# slaveV11.net
KiCad netlist of a schematic drawn in EAGLE
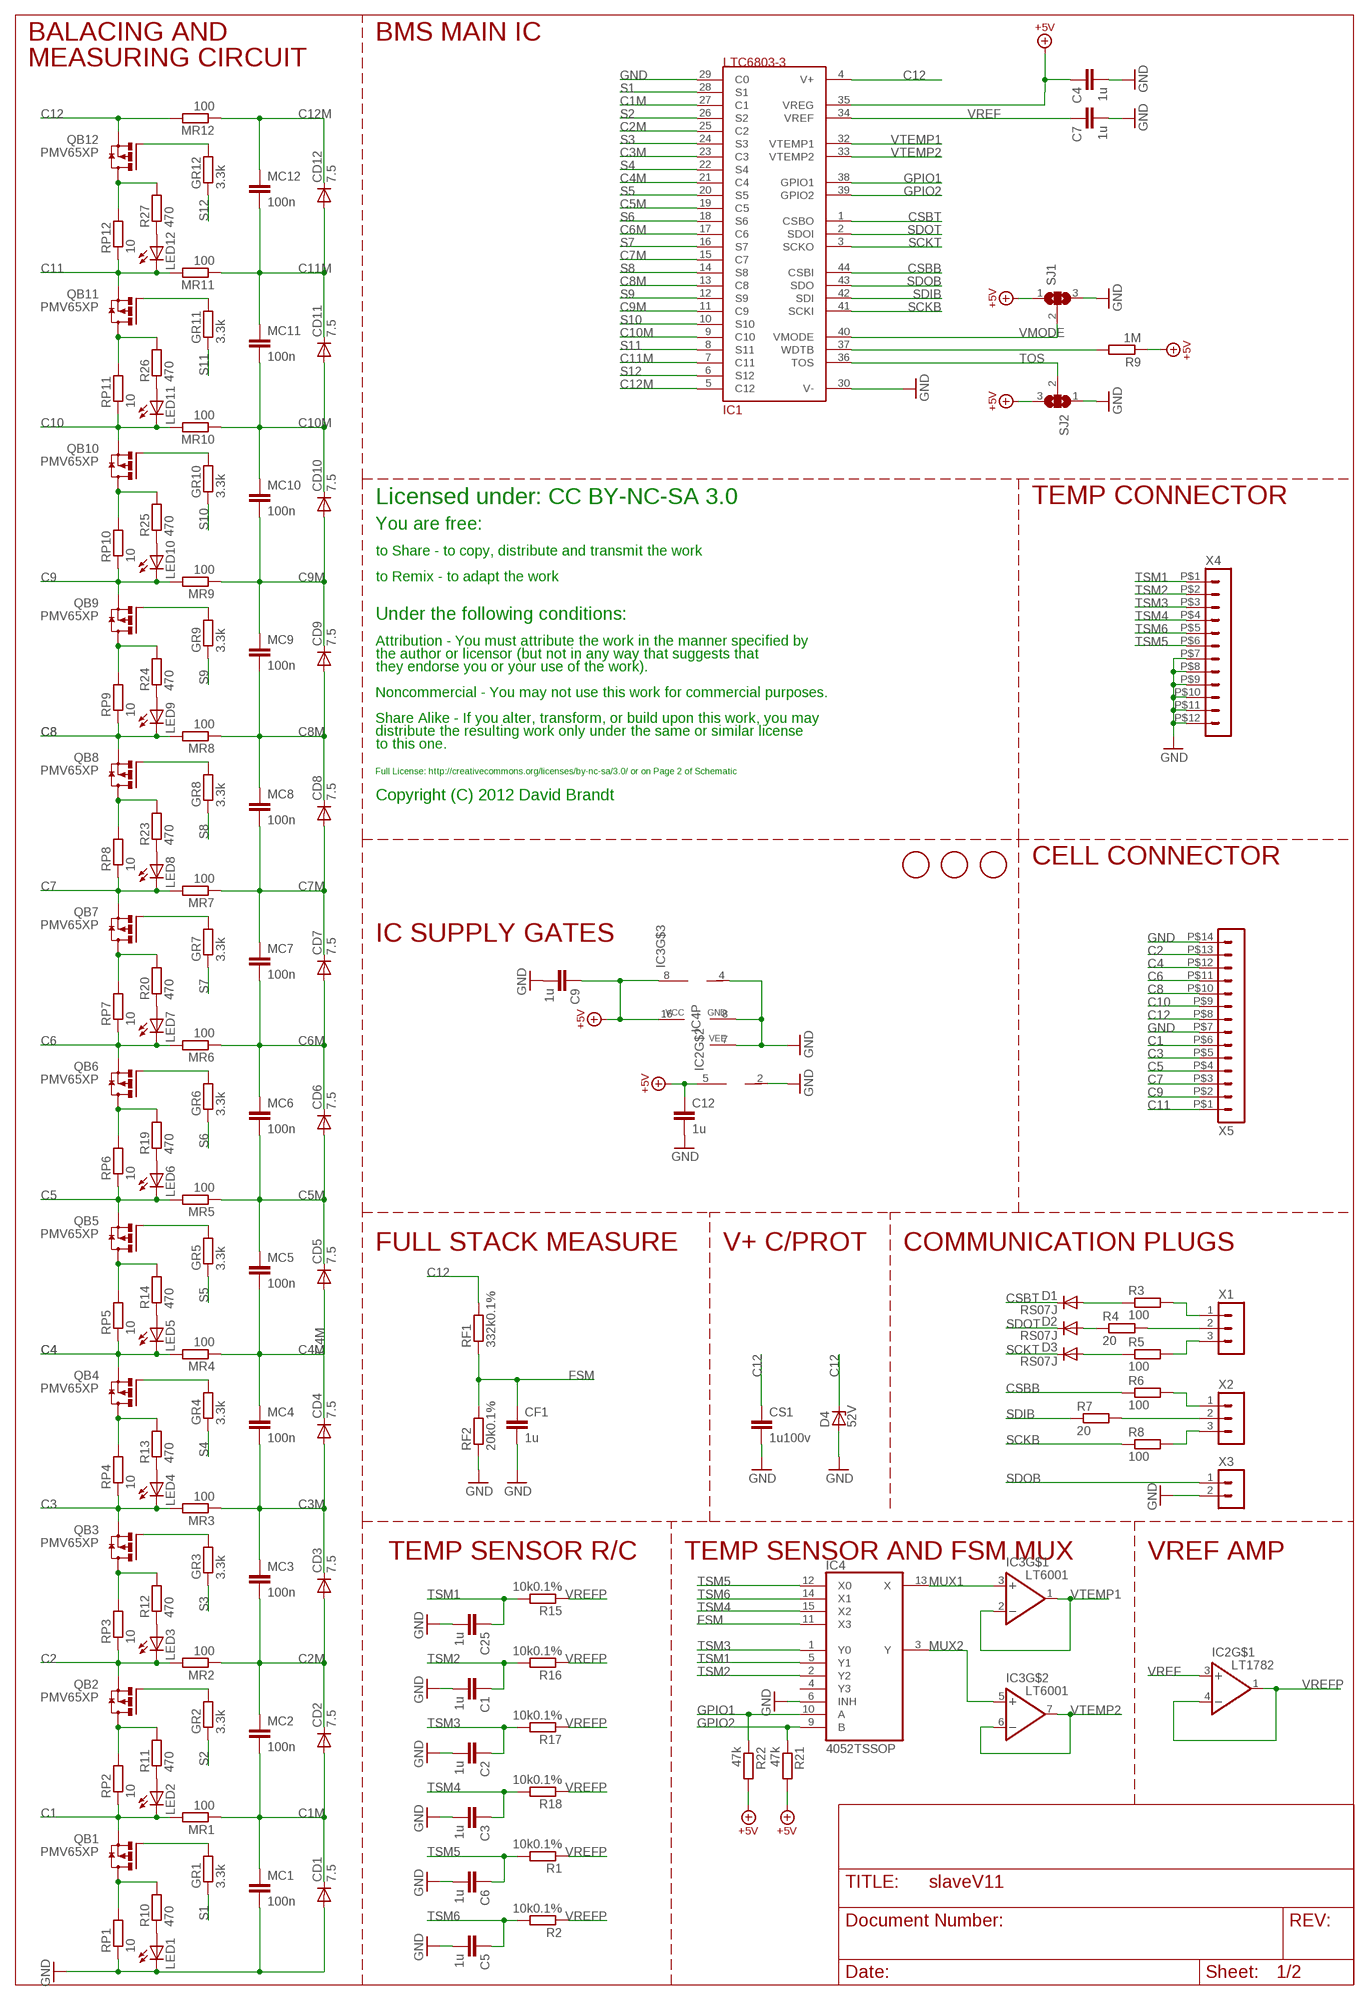
[diagram p0: schematic, sheet 1]
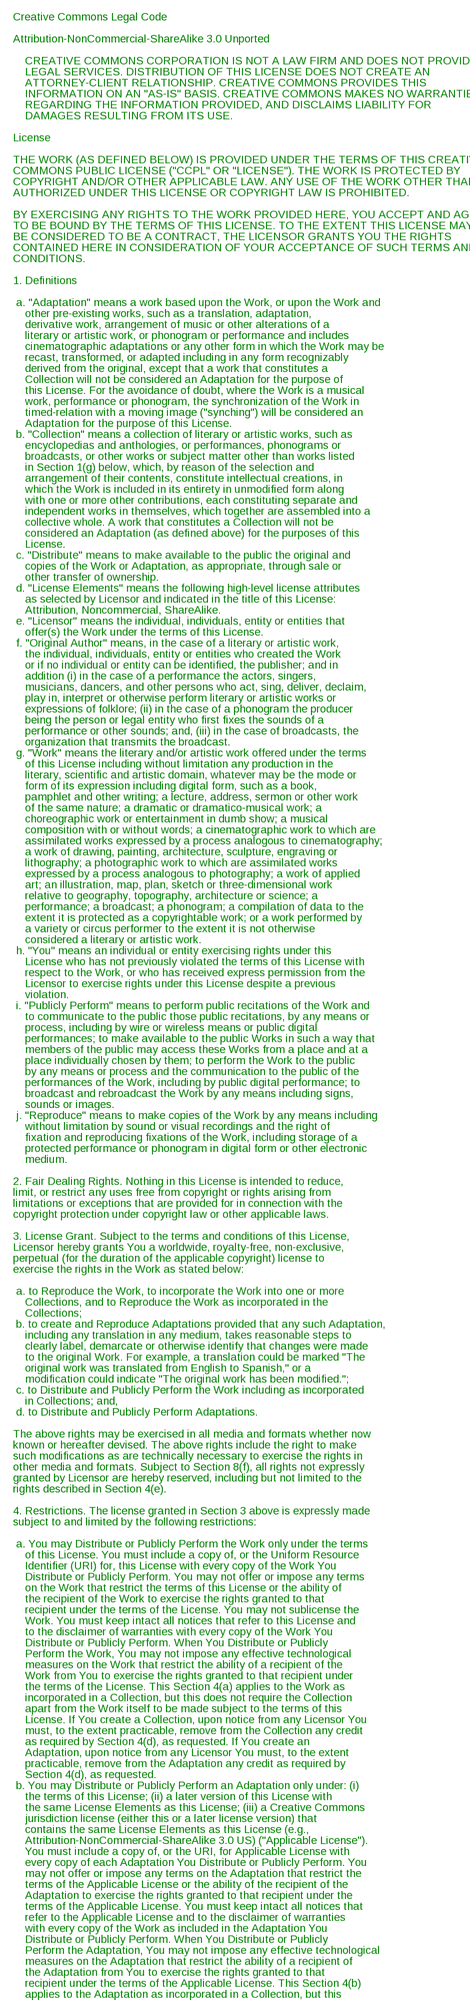
[diagram p1: schematic, sheet 2, part 1 of 2]
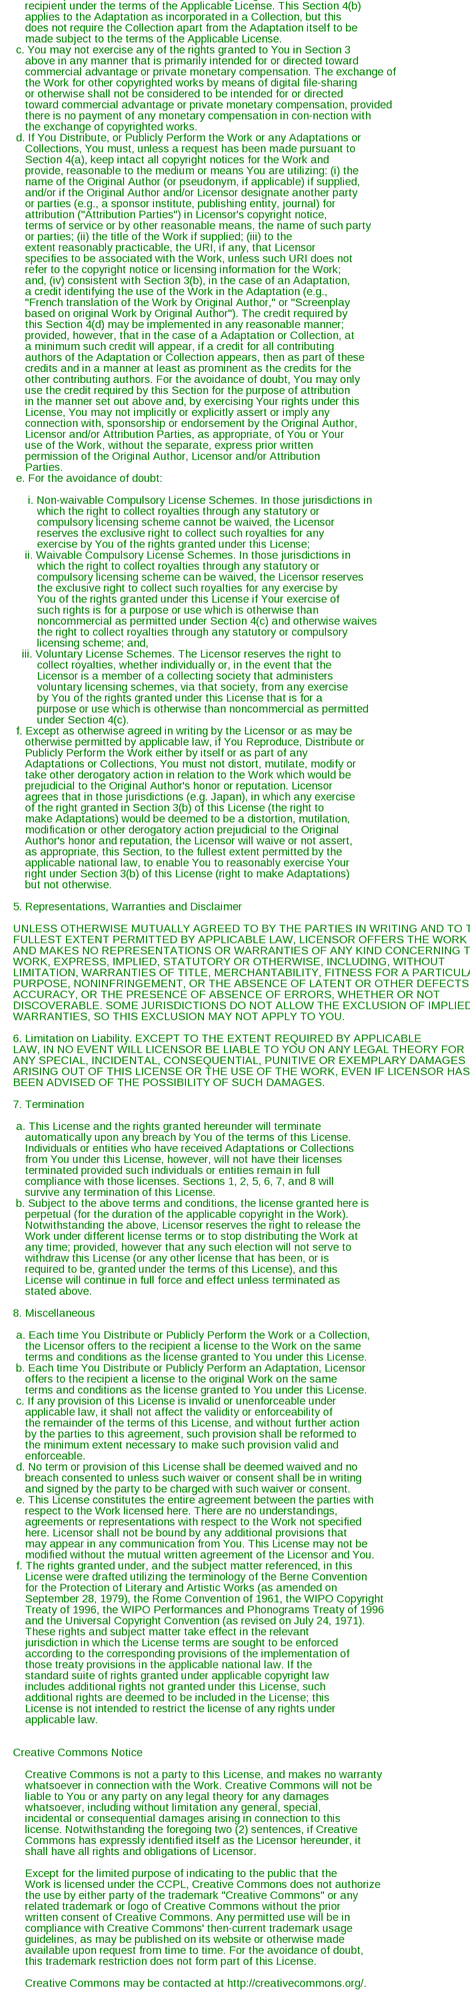
[diagram p2: schematic, sheet 2, part 2 of 2]

(export (version "E")
  (design (tool "Eeschema 10.0.6"))
  (components
    (comp (ref "C1")
      (value "1u")
      (footprint "eagle-import:C0603")
      (libsource (lib "eagle-import") (part "C-EUC0603"))
    )
    (comp (ref "C2")
      (value "1u")
      (footprint "eagle-import:C0603")
      (libsource (lib "eagle-import") (part "C-EUC0603"))
    )
    (comp (ref "C3")
      (value "1u")
      (footprint "eagle-import:C0603")
      (libsource (lib "eagle-import") (part "C-EUC0603"))
    )
    (comp (ref "C4")
      (value "1u")
      (footprint "eagle-import:C0603")
      (libsource (lib "eagle-import") (part "C-EUC0603"))
    )
    (comp (ref "C5")
      (value "1u")
      (footprint "eagle-import:C0603")
      (libsource (lib "eagle-import") (part "C-EUC0603"))
    )
    (comp (ref "C6")
      (value "1u")
      (footprint "eagle-import:C0603")
      (libsource (lib "eagle-import") (part "C-EUC0603"))
    )
    (comp (ref "C7")
      (value "1u")
      (footprint "eagle-import:C0603")
      (libsource (lib "eagle-import") (part "C-EUC0603"))
    )
    (comp (ref "C9")
      (value "1u")
      (footprint "eagle-import:C0603")
      (libsource (lib "eagle-import") (part "C-EUC0603"))
    )
    (comp (ref "C12")
      (value "1u")
      (footprint "eagle-import:C0603")
      (libsource (lib "eagle-import") (part "C-EUC0603"))
    )
    (comp (ref "C25")
      (value "1u")
      (footprint "eagle-import:C0603")
      (libsource (lib "eagle-import") (part "C-EUC0603"))
    )
    (comp (ref "CD1")
      (value "7.5")
      (footprint "eagle-import:SOD323-W")
      (libsource (lib "eagle-import") (part "DIODE-SOD323-W"))
    )
    (comp (ref "CD2")
      (value "7.5")
      (footprint "eagle-import:SOD323-W")
      (libsource (lib "eagle-import") (part "DIODE-SOD323-W"))
    )
    (comp (ref "CD3")
      (value "7.5")
      (footprint "eagle-import:SOD323-W")
      (libsource (lib "eagle-import") (part "DIODE-SOD323-W"))
    )
    (comp (ref "CD4")
      (value "7.5")
      (footprint "eagle-import:SOD323-W")
      (libsource (lib "eagle-import") (part "DIODE-SOD323-W"))
    )
    (comp (ref "CD5")
      (value "7.5")
      (footprint "eagle-import:SOD323-W")
      (libsource (lib "eagle-import") (part "DIODE-SOD323-W"))
    )
    (comp (ref "CD6")
      (value "7.5")
      (footprint "eagle-import:SOD323-W")
      (libsource (lib "eagle-import") (part "DIODE-SOD323-W"))
    )
    (comp (ref "CD7")
      (value "7.5")
      (footprint "eagle-import:SOD323-W")
      (libsource (lib "eagle-import") (part "DIODE-SOD323-W"))
    )
    (comp (ref "CD8")
      (value "7.5")
      (footprint "eagle-import:SOD323-W")
      (libsource (lib "eagle-import") (part "DIODE-SOD323-W"))
    )
    (comp (ref "CD9")
      (value "7.5")
      (footprint "eagle-import:SOD323-W")
      (libsource (lib "eagle-import") (part "DIODE-SOD323-W"))
    )
    (comp (ref "CD10")
      (value "7.5")
      (footprint "eagle-import:SOD323-W")
      (libsource (lib "eagle-import") (part "DIODE-SOD323-W"))
    )
    (comp (ref "CD11")
      (value "7.5")
      (footprint "eagle-import:SOD323-W")
      (libsource (lib "eagle-import") (part "DIODE-SOD323-W"))
    )
    (comp (ref "CD12")
      (value "7.5")
      (footprint "eagle-import:SOD323-W")
      (libsource (lib "eagle-import") (part "DIODE-SOD323-W"))
    )
    (comp (ref "CF1")
      (value "1u")
      (footprint "eagle-import:C0603")
      (libsource (lib "eagle-import") (part "C-EUC0603"))
    )
    (comp (ref "CS1")
      (value "1u100v")
      (footprint "eagle-import:C1206K")
      (libsource (lib "eagle-import") (part "C-EUC1206K"))
    )
    (comp (ref "D1")
      (value "RS07J")
      (footprint "eagle-import:DO-219AB")
      (libsource (lib "eagle-import") (part "RS07J"))
    )
    (comp (ref "D2")
      (value "RS07J")
      (footprint "eagle-import:DO-219AB")
      (libsource (lib "eagle-import") (part "RS07J"))
    )
    (comp (ref "D3")
      (value "RS07J")
      (footprint "eagle-import:DO-219AB")
      (libsource (lib "eagle-import") (part "RS07J"))
    )
    (comp (ref "D4")
      (value "52V")
      (footprint "eagle-import:SOD123")
      (libsource (lib "eagle-import") (part "ZENER-DIODESOD123"))
    )
    (comp (ref "GR1")
      (value "3.3k")
      (footprint "eagle-import:R0603")
      (libsource (lib "eagle-import") (part "rcl_R-EU_R0603"))
    )
    (comp (ref "GR2")
      (value "3.3k")
      (footprint "eagle-import:R0603")
      (libsource (lib "eagle-import") (part "rcl_R-EU_R0603"))
    )
    (comp (ref "GR3")
      (value "3.3k")
      (footprint "eagle-import:R0603")
      (libsource (lib "eagle-import") (part "rcl_R-EU_R0603"))
    )
    (comp (ref "GR4")
      (value "3.3k")
      (footprint "eagle-import:R0603")
      (libsource (lib "eagle-import") (part "rcl_R-EU_R0603"))
    )
    (comp (ref "GR5")
      (value "3.3k")
      (footprint "eagle-import:R0603")
      (libsource (lib "eagle-import") (part "rcl_R-EU_R0603"))
    )
    (comp (ref "GR6")
      (value "3.3k")
      (footprint "eagle-import:R0603")
      (libsource (lib "eagle-import") (part "rcl_R-EU_R0603"))
    )
    (comp (ref "GR7")
      (value "3.3k")
      (footprint "eagle-import:R0603")
      (libsource (lib "eagle-import") (part "rcl_R-EU_R0603"))
    )
    (comp (ref "GR8")
      (value "3.3k")
      (footprint "eagle-import:R0603")
      (libsource (lib "eagle-import") (part "rcl_R-EU_R0603"))
    )
    (comp (ref "GR9")
      (value "3.3k")
      (footprint "eagle-import:R0603")
      (libsource (lib "eagle-import") (part "rcl_R-EU_R0603"))
    )
    (comp (ref "GR10")
      (value "3.3k")
      (footprint "eagle-import:R0603")
      (libsource (lib "eagle-import") (part "rcl_R-EU_R0603"))
    )
    (comp (ref "GR11")
      (value "3.3k")
      (footprint "eagle-import:R0603")
      (libsource (lib "eagle-import") (part "rcl_R-EU_R0603"))
    )
    (comp (ref "GR12")
      (value "3.3k")
      (footprint "eagle-import:R0603")
      (libsource (lib "eagle-import") (part "rcl_R-EU_R0603"))
    )
    (comp (ref "IC1")
      (value "LTC6803-3")
      (footprint "eagle-import:44SSOP")
      (libsource (lib "eagle-import") (part "LTC6803-3"))
    )
    (comp (ref "IC2")
      (value "LT1782")
      (footprint "eagle-import:SOT23-5")
      (libsource (lib "eagle-import") (part "LT1782"))
    )
    (comp (ref "IC3")
      (value "LT6001")
      (footprint "eagle-import:MS8")
      (libsource (lib "eagle-import") (part "LT6004"))
    )
    (comp (ref "IC4")
      (value "4052TSSOP")
      (footprint "eagle-import:TSSOP16")
      (libsource (lib "eagle-import") (part "4052TSSOP"))
    )
    (comp (ref "LED1")
      (value "LEDCHIPLED_0805")
      (footprint "eagle-import:CHIPLED_0805")
      (libsource (lib "eagle-import") (part "LEDCHIPLED_0805"))
    )
    (comp (ref "LED2")
      (value "LEDCHIPLED_0805")
      (footprint "eagle-import:CHIPLED_0805")
      (libsource (lib "eagle-import") (part "LEDCHIPLED_0805"))
    )
    (comp (ref "LED3")
      (value "LEDCHIPLED_0805")
      (footprint "eagle-import:CHIPLED_0805")
      (libsource (lib "eagle-import") (part "LEDCHIPLED_0805"))
    )
    (comp (ref "LED4")
      (value "LEDCHIPLED_0805")
      (footprint "eagle-import:CHIPLED_0805")
      (libsource (lib "eagle-import") (part "LEDCHIPLED_0805"))
    )
    (comp (ref "LED5")
      (value "LEDCHIPLED_0805")
      (footprint "eagle-import:CHIPLED_0805")
      (libsource (lib "eagle-import") (part "LEDCHIPLED_0805"))
    )
    (comp (ref "LED6")
      (value "LEDCHIPLED_0805")
      (footprint "eagle-import:CHIPLED_0805")
      (libsource (lib "eagle-import") (part "LEDCHIPLED_0805"))
    )
    (comp (ref "LED7")
      (value "LEDCHIPLED_0805")
      (footprint "eagle-import:CHIPLED_0805")
      (libsource (lib "eagle-import") (part "LEDCHIPLED_0805"))
    )
    (comp (ref "LED8")
      (value "LEDCHIPLED_0805")
      (footprint "eagle-import:CHIPLED_0805")
      (libsource (lib "eagle-import") (part "LEDCHIPLED_0805"))
    )
    (comp (ref "LED9")
      (value "LEDCHIPLED_0805")
      (footprint "eagle-import:CHIPLED_0805")
      (libsource (lib "eagle-import") (part "LEDCHIPLED_0805"))
    )
    (comp (ref "LED10")
      (value "LEDCHIPLED_0805")
      (footprint "eagle-import:CHIPLED_0805")
      (libsource (lib "eagle-import") (part "LEDCHIPLED_0805"))
    )
    (comp (ref "LED11")
      (value "LEDCHIPLED_0805")
      (footprint "eagle-import:CHIPLED_0805")
      (libsource (lib "eagle-import") (part "LEDCHIPLED_0805"))
    )
    (comp (ref "LED12")
      (value "LEDCHIPLED_0805")
      (footprint "eagle-import:CHIPLED_0805")
      (libsource (lib "eagle-import") (part "LEDCHIPLED_0805"))
    )
    (comp (ref "MC1")
      (value "100n")
      (footprint "eagle-import:C1206")
      (libsource (lib "eagle-import") (part "C-EUC1206"))
    )
    (comp (ref "MC2")
      (value "100n")
      (footprint "eagle-import:C1206")
      (libsource (lib "eagle-import") (part "C-EUC1206"))
    )
    (comp (ref "MC3")
      (value "100n")
      (footprint "eagle-import:C1206")
      (libsource (lib "eagle-import") (part "C-EUC1206"))
    )
    (comp (ref "MC4")
      (value "100n")
      (footprint "eagle-import:C1206")
      (libsource (lib "eagle-import") (part "C-EUC1206"))
    )
    (comp (ref "MC5")
      (value "100n")
      (footprint "eagle-import:C1206")
      (libsource (lib "eagle-import") (part "C-EUC1206"))
    )
    (comp (ref "MC6")
      (value "100n")
      (footprint "eagle-import:C1206")
      (libsource (lib "eagle-import") (part "C-EUC1206"))
    )
    (comp (ref "MC7")
      (value "100n")
      (footprint "eagle-import:C1206")
      (libsource (lib "eagle-import") (part "C-EUC1206"))
    )
    (comp (ref "MC8")
      (value "100n")
      (footprint "eagle-import:C1206")
      (libsource (lib "eagle-import") (part "C-EUC1206"))
    )
    (comp (ref "MC9")
      (value "100n")
      (footprint "eagle-import:C1206")
      (libsource (lib "eagle-import") (part "C-EUC1206"))
    )
    (comp (ref "MC10")
      (value "100n")
      (footprint "eagle-import:C1206")
      (libsource (lib "eagle-import") (part "C-EUC1206"))
    )
    (comp (ref "MC11")
      (value "100n")
      (footprint "eagle-import:C1206")
      (libsource (lib "eagle-import") (part "C-EUC1206"))
    )
    (comp (ref "MC12")
      (value "100n")
      (footprint "eagle-import:C1206")
      (libsource (lib "eagle-import") (part "C-EUC1206"))
    )
    (comp (ref "MR1")
      (value "100")
      (footprint "eagle-import:R0603")
      (libsource (lib "eagle-import") (part "rcl_R-EU_R0603"))
    )
    (comp (ref "MR2")
      (value "100")
      (footprint "eagle-import:R0603")
      (libsource (lib "eagle-import") (part "rcl_R-EU_R0603"))
    )
    (comp (ref "MR3")
      (value "100")
      (footprint "eagle-import:R0603")
      (libsource (lib "eagle-import") (part "rcl_R-EU_R0603"))
    )
    (comp (ref "MR4")
      (value "100")
      (footprint "eagle-import:R0603")
      (libsource (lib "eagle-import") (part "rcl_R-EU_R0603"))
    )
    (comp (ref "MR5")
      (value "100")
      (footprint "eagle-import:R0603")
      (libsource (lib "eagle-import") (part "rcl_R-EU_R0603"))
    )
    (comp (ref "MR6")
      (value "100")
      (footprint "eagle-import:R0603")
      (libsource (lib "eagle-import") (part "rcl_R-EU_R0603"))
    )
    (comp (ref "MR7")
      (value "100")
      (footprint "eagle-import:R0603")
      (libsource (lib "eagle-import") (part "rcl_R-EU_R0603"))
    )
    (comp (ref "MR8")
      (value "100")
      (footprint "eagle-import:R0603")
      (libsource (lib "eagle-import") (part "rcl_R-EU_R0603"))
    )
    (comp (ref "MR9")
      (value "100")
      (footprint "eagle-import:R0603")
      (libsource (lib "eagle-import") (part "rcl_R-EU_R0603"))
    )
    (comp (ref "MR10")
      (value "100")
      (footprint "eagle-import:R0603")
      (libsource (lib "eagle-import") (part "rcl_R-EU_R0603"))
    )
    (comp (ref "MR11")
      (value "100")
      (footprint "eagle-import:R0603")
      (libsource (lib "eagle-import") (part "rcl_R-EU_R0603"))
    )
    (comp (ref "MR12")
      (value "100")
      (footprint "eagle-import:R0603")
      (libsource (lib "eagle-import") (part "rcl_R-EU_R0603"))
    )
    (comp (ref "QB1")
      (value "PMV65XP")
      (footprint "eagle-import:SUPER-SOT3")
      (libsource (lib "eagle-import") (part "FDN360P"))
    )
    (comp (ref "QB2")
      (value "PMV65XP")
      (footprint "eagle-import:SUPER-SOT3")
      (libsource (lib "eagle-import") (part "FDN360P"))
    )
    (comp (ref "QB3")
      (value "PMV65XP")
      (footprint "eagle-import:SUPER-SOT3")
      (libsource (lib "eagle-import") (part "FDN360P"))
    )
    (comp (ref "QB4")
      (value "PMV65XP")
      (footprint "eagle-import:SUPER-SOT3")
      (libsource (lib "eagle-import") (part "FDN360P"))
    )
    (comp (ref "QB5")
      (value "PMV65XP")
      (footprint "eagle-import:SUPER-SOT3")
      (libsource (lib "eagle-import") (part "FDN360P"))
    )
    (comp (ref "QB6")
      (value "PMV65XP")
      (footprint "eagle-import:SUPER-SOT3")
      (libsource (lib "eagle-import") (part "FDN360P"))
    )
    (comp (ref "QB7")
      (value "PMV65XP")
      (footprint "eagle-import:SUPER-SOT3")
      (libsource (lib "eagle-import") (part "FDN360P"))
    )
    (comp (ref "QB8")
      (value "PMV65XP")
      (footprint "eagle-import:SUPER-SOT3")
      (libsource (lib "eagle-import") (part "FDN360P"))
    )
    (comp (ref "QB9")
      (value "PMV65XP")
      (footprint "eagle-import:SUPER-SOT3")
      (libsource (lib "eagle-import") (part "FDN360P"))
    )
    (comp (ref "QB10")
      (value "PMV65XP")
      (footprint "eagle-import:SUPER-SOT3")
      (libsource (lib "eagle-import") (part "FDN360P"))
    )
    (comp (ref "QB11")
      (value "PMV65XP")
      (footprint "eagle-import:SUPER-SOT3")
      (libsource (lib "eagle-import") (part "FDN360P"))
    )
    (comp (ref "QB12")
      (value "PMV65XP")
      (footprint "eagle-import:SUPER-SOT3")
      (libsource (lib "eagle-import") (part "FDN360P"))
    )
    (comp (ref "R1")
      (value "10k0.1%")
      (footprint "eagle-import:R0603")
      (libsource (lib "eagle-import") (part "rcl_R-EU_R0603"))
    )
    (comp (ref "R2")
      (value "10k0.1%")
      (footprint "eagle-import:R0603")
      (libsource (lib "eagle-import") (part "rcl_R-EU_R0603"))
    )
    (comp (ref "R3")
      (value "100")
      (footprint "eagle-import:R0805")
      (libsource (lib "eagle-import") (part "rcl_R-EU_R0805"))
    )
    (comp (ref "R4")
      (value "20")
      (footprint "eagle-import:R0805")
      (libsource (lib "eagle-import") (part "rcl_R-EU_R0805"))
    )
    (comp (ref "R5")
      (value "100")
      (footprint "eagle-import:R0805")
      (libsource (lib "eagle-import") (part "rcl_R-EU_R0805"))
    )
    (comp (ref "R6")
      (value "100")
      (footprint "eagle-import:R0805")
      (libsource (lib "eagle-import") (part "rcl_R-EU_R0805"))
    )
    (comp (ref "R7")
      (value "20")
      (footprint "eagle-import:R0805")
      (libsource (lib "eagle-import") (part "rcl_R-EU_R0805"))
    )
    (comp (ref "R8")
      (value "100")
      (footprint "eagle-import:R0805")
      (libsource (lib "eagle-import") (part "rcl_R-EU_R0805"))
    )
    (comp (ref "R9")
      (value "1M")
      (footprint "eagle-import:R0603")
      (libsource (lib "eagle-import") (part "rcl_R-EU_R0603"))
    )
    (comp (ref "R10")
      (value "470")
      (footprint "eagle-import:R0603")
      (libsource (lib "eagle-import") (part "rcl_R-EU_R0603"))
    )
    (comp (ref "R11")
      (value "470")
      (footprint "eagle-import:R0603")
      (libsource (lib "eagle-import") (part "rcl_R-EU_R0603"))
    )
    (comp (ref "R12")
      (value "470")
      (footprint "eagle-import:R0603")
      (libsource (lib "eagle-import") (part "rcl_R-EU_R0603"))
    )
    (comp (ref "R13")
      (value "470")
      (footprint "eagle-import:R0603")
      (libsource (lib "eagle-import") (part "rcl_R-EU_R0603"))
    )
    (comp (ref "R14")
      (value "470")
      (footprint "eagle-import:R0603")
      (libsource (lib "eagle-import") (part "rcl_R-EU_R0603"))
    )
    (comp (ref "R15")
      (value "10k0.1%")
      (footprint "eagle-import:R0603")
      (libsource (lib "eagle-import") (part "rcl_R-EU_R0603"))
    )
    (comp (ref "R16")
      (value "10k0.1%")
      (footprint "eagle-import:R0603")
      (libsource (lib "eagle-import") (part "rcl_R-EU_R0603"))
    )
    (comp (ref "R17")
      (value "10k0.1%")
      (footprint "eagle-import:R0603")
      (libsource (lib "eagle-import") (part "rcl_R-EU_R0603"))
    )
    (comp (ref "R18")
      (value "10k0.1%")
      (footprint "eagle-import:R0603")
      (libsource (lib "eagle-import") (part "rcl_R-EU_R0603"))
    )
    (comp (ref "R19")
      (value "470")
      (footprint "eagle-import:R0603")
      (libsource (lib "eagle-import") (part "rcl_R-EU_R0603"))
    )
    (comp (ref "R20")
      (value "470")
      (footprint "eagle-import:R0603")
      (libsource (lib "eagle-import") (part "rcl_R-EU_R0603"))
    )
    (comp (ref "R21")
      (value "47k")
      (footprint "eagle-import:R0603")
      (libsource (lib "eagle-import") (part "rcl_R-EU_R0603"))
    )
    (comp (ref "R22")
      (value "47k")
      (footprint "eagle-import:R0603")
      (libsource (lib "eagle-import") (part "rcl_R-EU_R0603"))
    )
    (comp (ref "R23")
      (value "470")
      (footprint "eagle-import:R0603")
      (libsource (lib "eagle-import") (part "rcl_R-EU_R0603"))
    )
    (comp (ref "R24")
      (value "470")
      (footprint "eagle-import:R0603")
      (libsource (lib "eagle-import") (part "rcl_R-EU_R0603"))
    )
    (comp (ref "R25")
      (value "470")
      (footprint "eagle-import:R0603")
      (libsource (lib "eagle-import") (part "rcl_R-EU_R0603"))
    )
    (comp (ref "R26")
      (value "470")
      (footprint "eagle-import:R0603")
      (libsource (lib "eagle-import") (part "rcl_R-EU_R0603"))
    )
    (comp (ref "R27")
      (value "470")
      (footprint "eagle-import:R0603")
      (libsource (lib "eagle-import") (part "rcl_R-EU_R0603"))
    )
    (comp (ref "REF1")
      (value "FIDUCIALMOUNT")
      (footprint "eagle-import:FIDUCIA-MOUNT")
      (libsource (lib "eagle-import") (part "FIDUCIALMOUNT"))
    )
    (comp (ref "REF2")
      (value "FIDUCIALMOUNT")
      (footprint "eagle-import:FIDUCIA-MOUNT")
      (libsource (lib "eagle-import") (part "FIDUCIALMOUNT"))
    )
    (comp (ref "REF3")
      (value "FIDUCIALMOUNT")
      (footprint "eagle-import:FIDUCIA-MOUNT")
      (libsource (lib "eagle-import") (part "FIDUCIALMOUNT"))
    )
    (comp (ref "RF1")
      (value "332k0.1%")
      (footprint "eagle-import:R0603")
      (libsource (lib "eagle-import") (part "rcl_R-EU_R0603"))
    )
    (comp (ref "RF2")
      (value "20k0.1%")
      (footprint "eagle-import:R0603")
      (libsource (lib "eagle-import") (part "rcl_R-EU_R0603"))
    )
    (comp (ref "RP1")
      (value "10")
      (footprint "eagle-import:SM_3")
      (libsource (lib "eagle-import") (part "R-EU_SM_3"))
    )
    (comp (ref "RP2")
      (value "10")
      (footprint "eagle-import:SM_3")
      (libsource (lib "eagle-import") (part "R-EU_SM_3"))
    )
    (comp (ref "RP3")
      (value "10")
      (footprint "eagle-import:SM_3")
      (libsource (lib "eagle-import") (part "R-EU_SM_3"))
    )
    (comp (ref "RP4")
      (value "10")
      (footprint "eagle-import:SM_3")
      (libsource (lib "eagle-import") (part "R-EU_SM_3"))
    )
    (comp (ref "RP5")
      (value "10")
      (footprint "eagle-import:SM_3")
      (libsource (lib "eagle-import") (part "R-EU_SM_3"))
    )
    (comp (ref "RP6")
      (value "10")
      (footprint "eagle-import:SM_3")
      (libsource (lib "eagle-import") (part "R-EU_SM_3"))
    )
    (comp (ref "RP7")
      (value "10")
      (footprint "eagle-import:SM_3")
      (libsource (lib "eagle-import") (part "R-EU_SM_3"))
    )
    (comp (ref "RP8")
      (value "10")
      (footprint "eagle-import:SM_3")
      (libsource (lib "eagle-import") (part "R-EU_SM_3"))
    )
    (comp (ref "RP9")
      (value "10")
      (footprint "eagle-import:SM_3")
      (libsource (lib "eagle-import") (part "R-EU_SM_3"))
    )
    (comp (ref "RP10")
      (value "10")
      (footprint "eagle-import:SM_3")
      (libsource (lib "eagle-import") (part "R-EU_SM_3"))
    )
    (comp (ref "RP11")
      (value "10")
      (footprint "eagle-import:SM_3")
      (libsource (lib "eagle-import") (part "R-EU_SM_3"))
    )
    (comp (ref "RP12")
      (value "10")
      (footprint "eagle-import:SM_3")
      (libsource (lib "eagle-import") (part "R-EU_SM_3"))
    )
    (comp (ref "SJ1")
      (value "SJ2W")
      (footprint "eagle-import:SJ_2")
      (libsource (lib "eagle-import") (part "SJ2W"))
    )
    (comp (ref "SJ2")
      (value "SJ2W")
      (footprint "eagle-import:SJ_2")
      (libsource (lib "eagle-import") (part "SJ2W"))
    )
    (comp (ref "X1")
      (value "HEADER_POS3_43650-0315")
      (footprint "eagle-import:43650-0315")
      (libsource (lib "eagle-import") (part "HEADER_POS3_?43650-0315"))
    )
    (comp (ref "X2")
      (value "HEADER_POS3_43650-0315")
      (footprint "eagle-import:43650-0315")
      (libsource (lib "eagle-import") (part "HEADER_POS3_?43650-0315"))
    )
    (comp (ref "X3")
      (value "HEADER_POS2_43650-0215")
      (footprint "eagle-import:43650-0215")
      (libsource (lib "eagle-import") (part "HEADER_POS2_?43650-0215"))
    )
    (comp (ref "X4")
      (value "HEADER_POS12_43045-1212")
      (footprint "eagle-import:43045-1212")
      (libsource (lib "eagle-import") (part "HEADER_POS12_?43045-1212"))
    )
    (comp (ref "X5")
      (value "HEADER_POS14_43045-1412")
      (footprint "eagle-import:43045-1412")
      (libsource (lib "eagle-import") (part "HEADER_POS14_?43045-1412"))
    )
  )
  (nets
    (net (code "1") (name "+5V") (class "Default")
      (node (ref "C12") (pin "1") (pinfunction "1_1") (pintype "passive"))
      (node (ref "C4") (pin "1") (pinfunction "1_1") (pintype "passive"))
      (node (ref "C9") (pin "1") (pinfunction "1_1") (pintype "passive"))
      (node (ref "IC1") (pin "35") (pinfunction "VREG_35") (pintype "bidirectional"))
      (node (ref "IC2") (pin "5") (pinfunction "V+_5") (pintype "power_in"))
      (node (ref "IC3") (pin "8") (pinfunction "V+_8") (pintype "power_in"))
      (node (ref "IC4") (pin "16") (pinfunction "VCC_16") (pintype "power_in"))
      (node (ref "R21") (pin "2") (pinfunction "2_2") (pintype "passive"))
      (node (ref "R22") (pin "2") (pinfunction "2_2") (pintype "passive"))
      (node (ref "R9") (pin "1") (pinfunction "1_1") (pintype "passive"))
      (node (ref "SJ1") (pin "1") (pinfunction "1_1") (pintype "passive"))
      (node (ref "SJ2") (pin "3") (pinfunction "3_3") (pintype "passive"))
    )
    (net (code "2") (name "C1") (class "Default")
      (node (ref "LED2") (pin "C") (pinfunction "C_C") (pintype "passive"))
      (node (ref "MR1") (pin "2") (pinfunction "2_2") (pintype "passive"))
      (node (ref "QB1") (pin "2") (pinfunction "S_2") (pintype "passive"))
      (node (ref "RP2") (pin "P$1") (pinfunction "1_P$1") (pintype "passive"))
      (node (ref "X5") (pin "P$6") (pinfunction "6_P$6") (pintype "passive"))
    )
    (net (code "3") (name "C1M") (class "Default")
      (node (ref "CD1") (pin "C") (pinfunction "C_C") (pintype "passive"))
      (node (ref "CD2") (pin "A") (pinfunction "A_A") (pintype "passive"))
      (node (ref "IC1") (pin "27") (pinfunction "C1_27") (pintype "bidirectional"))
      (node (ref "MC1") (pin "1") (pinfunction "1_1") (pintype "passive"))
      (node (ref "MC2") (pin "2") (pinfunction "2_2") (pintype "passive"))
      (node (ref "MR1") (pin "1") (pinfunction "1_1") (pintype "passive"))
    )
    (net (code "4") (name "C2") (class "Default")
      (node (ref "LED3") (pin "C") (pinfunction "C_C") (pintype "passive"))
      (node (ref "MR2") (pin "2") (pinfunction "2_2") (pintype "passive"))
      (node (ref "QB2") (pin "2") (pinfunction "S_2") (pintype "passive"))
      (node (ref "RP3") (pin "P$1") (pinfunction "1_P$1") (pintype "passive"))
      (node (ref "X5") (pin "P$13") (pinfunction "13_P$13") (pintype "passive"))
    )
    (net (code "5") (name "C2M") (class "Default")
      (node (ref "CD2") (pin "C") (pinfunction "C_C") (pintype "passive"))
      (node (ref "CD3") (pin "A") (pinfunction "A_A") (pintype "passive"))
      (node (ref "IC1") (pin "25") (pinfunction "C2_25") (pintype "bidirectional"))
      (node (ref "MC2") (pin "1") (pinfunction "1_1") (pintype "passive"))
      (node (ref "MC3") (pin "2") (pinfunction "2_2") (pintype "passive"))
      (node (ref "MR2") (pin "1") (pinfunction "1_1") (pintype "passive"))
    )
    (net (code "6") (name "C3") (class "Default")
      (node (ref "LED4") (pin "C") (pinfunction "C_C") (pintype "passive"))
      (node (ref "MR3") (pin "2") (pinfunction "2_2") (pintype "passive"))
      (node (ref "QB3") (pin "2") (pinfunction "S_2") (pintype "passive"))
      (node (ref "RP4") (pin "P$1") (pinfunction "1_P$1") (pintype "passive"))
      (node (ref "X5") (pin "P$5") (pinfunction "5_P$5") (pintype "passive"))
    )
    (net (code "7") (name "C3M") (class "Default")
      (node (ref "CD3") (pin "C") (pinfunction "C_C") (pintype "passive"))
      (node (ref "CD4") (pin "A") (pinfunction "A_A") (pintype "passive"))
      (node (ref "IC1") (pin "23") (pinfunction "C3_23") (pintype "bidirectional"))
      (node (ref "MC3") (pin "1") (pinfunction "1_1") (pintype "passive"))
      (node (ref "MC4") (pin "2") (pinfunction "2_2") (pintype "passive"))
      (node (ref "MR3") (pin "1") (pinfunction "1_1") (pintype "passive"))
    )
    (net (code "8") (name "C4") (class "Default")
      (node (ref "LED5") (pin "C") (pinfunction "C_C") (pintype "passive"))
      (node (ref "MR4") (pin "2") (pinfunction "2_2") (pintype "passive"))
      (node (ref "QB4") (pin "2") (pinfunction "S_2") (pintype "passive"))
      (node (ref "RP5") (pin "P$1") (pinfunction "1_P$1") (pintype "passive"))
      (node (ref "X5") (pin "P$12") (pinfunction "12_P$12") (pintype "passive"))
    )
    (net (code "9") (name "C4M") (class "Default")
      (node (ref "CD4") (pin "C") (pinfunction "C_C") (pintype "passive"))
      (node (ref "CD5") (pin "A") (pinfunction "A_A") (pintype "passive"))
      (node (ref "IC1") (pin "21") (pinfunction "C4_21") (pintype "bidirectional"))
      (node (ref "MC4") (pin "1") (pinfunction "1_1") (pintype "passive"))
      (node (ref "MC5") (pin "2") (pinfunction "2_2") (pintype "passive"))
      (node (ref "MR4") (pin "1") (pinfunction "1_1") (pintype "passive"))
    )
    (net (code "10") (name "C5") (class "Default")
      (node (ref "LED6") (pin "C") (pinfunction "C_C") (pintype "passive"))
      (node (ref "MR5") (pin "2") (pinfunction "2_2") (pintype "passive"))
      (node (ref "QB5") (pin "2") (pinfunction "S_2") (pintype "passive"))
      (node (ref "RP6") (pin "P$1") (pinfunction "1_P$1") (pintype "passive"))
      (node (ref "X5") (pin "P$4") (pinfunction "4_P$4") (pintype "passive"))
    )
    (net (code "11") (name "C5M") (class "Default")
      (node (ref "CD5") (pin "C") (pinfunction "C_C") (pintype "passive"))
      (node (ref "CD6") (pin "A") (pinfunction "A_A") (pintype "passive"))
      (node (ref "IC1") (pin "19") (pinfunction "C5_19") (pintype "bidirectional"))
      (node (ref "MC5") (pin "1") (pinfunction "1_1") (pintype "passive"))
      (node (ref "MC6") (pin "2") (pinfunction "2_2") (pintype "passive"))
      (node (ref "MR5") (pin "1") (pinfunction "1_1") (pintype "passive"))
    )
    (net (code "12") (name "C6") (class "Default")
      (node (ref "LED7") (pin "C") (pinfunction "C_C") (pintype "passive"))
      (node (ref "MR6") (pin "2") (pinfunction "2_2") (pintype "passive"))
      (node (ref "QB6") (pin "2") (pinfunction "S_2") (pintype "passive"))
      (node (ref "RP7") (pin "P$1") (pinfunction "1_P$1") (pintype "passive"))
      (node (ref "X5") (pin "P$11") (pinfunction "11_P$11") (pintype "passive"))
    )
    (net (code "13") (name "C6M") (class "Default")
      (node (ref "CD6") (pin "C") (pinfunction "C_C") (pintype "passive"))
      (node (ref "CD7") (pin "A") (pinfunction "A_A") (pintype "passive"))
      (node (ref "IC1") (pin "17") (pinfunction "C6_17") (pintype "bidirectional"))
      (node (ref "MC6") (pin "1") (pinfunction "1_1") (pintype "passive"))
      (node (ref "MC7") (pin "2") (pinfunction "2_2") (pintype "passive"))
      (node (ref "MR6") (pin "1") (pinfunction "1_1") (pintype "passive"))
    )
    (net (code "14") (name "C7") (class "Default")
      (node (ref "LED8") (pin "C") (pinfunction "C_C") (pintype "passive"))
      (node (ref "MR7") (pin "2") (pinfunction "2_2") (pintype "passive"))
      (node (ref "QB7") (pin "2") (pinfunction "S_2") (pintype "passive"))
      (node (ref "RP8") (pin "P$1") (pinfunction "1_P$1") (pintype "passive"))
      (node (ref "X5") (pin "P$3") (pinfunction "3_P$3") (pintype "passive"))
    )
    (net (code "15") (name "C7M") (class "Default")
      (node (ref "CD7") (pin "C") (pinfunction "C_C") (pintype "passive"))
      (node (ref "CD8") (pin "A") (pinfunction "A_A") (pintype "passive"))
      (node (ref "IC1") (pin "15") (pinfunction "C7_15") (pintype "bidirectional"))
      (node (ref "MC7") (pin "1") (pinfunction "1_1") (pintype "passive"))
      (node (ref "MC8") (pin "2") (pinfunction "2_2") (pintype "passive"))
      (node (ref "MR7") (pin "1") (pinfunction "1_1") (pintype "passive"))
    )
    (net (code "16") (name "C8") (class "Default")
      (node (ref "LED9") (pin "C") (pinfunction "C_C") (pintype "passive"))
      (node (ref "MR8") (pin "2") (pinfunction "2_2") (pintype "passive"))
      (node (ref "QB8") (pin "2") (pinfunction "S_2") (pintype "passive"))
      (node (ref "RP9") (pin "P$1") (pinfunction "1_P$1") (pintype "passive"))
      (node (ref "X5") (pin "P$10") (pinfunction "10_P$10") (pintype "passive"))
    )
    (net (code "17") (name "C8M") (class "Default")
      (node (ref "CD8") (pin "C") (pinfunction "C_C") (pintype "passive"))
      (node (ref "CD9") (pin "A") (pinfunction "A_A") (pintype "passive"))
      (node (ref "IC1") (pin "13") (pinfunction "C8_13") (pintype "bidirectional"))
      (node (ref "MC8") (pin "1") (pinfunction "1_1") (pintype "passive"))
      (node (ref "MC9") (pin "2") (pinfunction "2_2") (pintype "passive"))
      (node (ref "MR8") (pin "1") (pinfunction "1_1") (pintype "passive"))
    )
    (net (code "18") (name "C9") (class "Default")
      (node (ref "LED10") (pin "C") (pinfunction "C_C") (pintype "passive"))
      (node (ref "MR9") (pin "2") (pinfunction "2_2") (pintype "passive"))
      (node (ref "QB9") (pin "2") (pinfunction "S_2") (pintype "passive"))
      (node (ref "RP10") (pin "P$1") (pinfunction "1_P$1") (pintype "passive"))
      (node (ref "X5") (pin "P$2") (pinfunction "2_P$2") (pintype "passive"))
    )
    (net (code "19") (name "C9M") (class "Default")
      (node (ref "CD10") (pin "A") (pinfunction "A_A") (pintype "passive"))
      (node (ref "CD9") (pin "C") (pinfunction "C_C") (pintype "passive"))
      (node (ref "IC1") (pin "11") (pinfunction "C9_11") (pintype "bidirectional"))
      (node (ref "MC10") (pin "2") (pinfunction "2_2") (pintype "passive"))
      (node (ref "MC9") (pin "1") (pinfunction "1_1") (pintype "passive"))
      (node (ref "MR9") (pin "1") (pinfunction "1_1") (pintype "passive"))
    )
    (net (code "20") (name "C10") (class "Default")
      (node (ref "LED11") (pin "C") (pinfunction "C_C") (pintype "passive"))
      (node (ref "MR10") (pin "2") (pinfunction "2_2") (pintype "passive"))
      (node (ref "QB10") (pin "2") (pinfunction "S_2") (pintype "passive"))
      (node (ref "RP11") (pin "P$1") (pinfunction "1_P$1") (pintype "passive"))
      (node (ref "X5") (pin "P$9") (pinfunction "9_P$9") (pintype "passive"))
    )
    (net (code "21") (name "C10M") (class "Default")
      (node (ref "CD10") (pin "C") (pinfunction "C_C") (pintype "passive"))
      (node (ref "CD11") (pin "A") (pinfunction "A_A") (pintype "passive"))
      (node (ref "IC1") (pin "9") (pinfunction "C10_9") (pintype "bidirectional"))
      (node (ref "MC10") (pin "1") (pinfunction "1_1") (pintype "passive"))
      (node (ref "MC11") (pin "2") (pinfunction "2_2") (pintype "passive"))
      (node (ref "MR10") (pin "1") (pinfunction "1_1") (pintype "passive"))
    )
    (net (code "22") (name "C11") (class "Default")
      (node (ref "LED12") (pin "C") (pinfunction "C_C") (pintype "passive"))
      (node (ref "MR11") (pin "2") (pinfunction "2_2") (pintype "passive"))
      (node (ref "QB11") (pin "2") (pinfunction "S_2") (pintype "passive"))
      (node (ref "RP12") (pin "P$1") (pinfunction "1_P$1") (pintype "passive"))
      (node (ref "X5") (pin "P$1") (pinfunction "1_P$1") (pintype "passive"))
    )
    (net (code "23") (name "C11M") (class "Default")
      (node (ref "CD11") (pin "C") (pinfunction "C_C") (pintype "passive"))
      (node (ref "CD12") (pin "A") (pinfunction "A_A") (pintype "passive"))
      (node (ref "IC1") (pin "7") (pinfunction "C11_7") (pintype "bidirectional"))
      (node (ref "MC11") (pin "1") (pinfunction "1_1") (pintype "passive"))
      (node (ref "MC12") (pin "2") (pinfunction "2_2") (pintype "passive"))
      (node (ref "MR11") (pin "1") (pinfunction "1_1") (pintype "passive"))
    )
    (net (code "24") (name "C12") (class "Default")
      (node (ref "CS1") (pin "1") (pinfunction "1_1") (pintype "passive"))
      (node (ref "D4") (pin "C") (pinfunction "C_C") (pintype "passive"))
      (node (ref "IC1") (pin "4") (pinfunction "V+_4") (pintype "bidirectional"))
      (node (ref "MR12") (pin "2") (pinfunction "2_2") (pintype "passive"))
      (node (ref "QB12") (pin "2") (pinfunction "S_2") (pintype "passive"))
      (node (ref "RF1") (pin "2") (pinfunction "2_2") (pintype "passive"))
      (node (ref "X5") (pin "P$8") (pinfunction "8_P$8") (pintype "passive"))
    )
    (net (code "25") (name "C12M") (class "Default")
      (node (ref "CD12") (pin "C") (pinfunction "C_C") (pintype "passive"))
      (node (ref "IC1") (pin "5") (pinfunction "C12_5") (pintype "bidirectional"))
      (node (ref "MC12") (pin "1") (pinfunction "1_1") (pintype "passive"))
      (node (ref "MR12") (pin "1") (pinfunction "1_1") (pintype "passive"))
    )
    (net (code "26") (name "CSBB") (class "Default")
      (node (ref "IC1") (pin "44") (pinfunction "CSBI_44") (pintype "bidirectional"))
      (node (ref "R6") (pin "1") (pinfunction "1_1") (pintype "passive"))
    )
    (net (code "27") (name "CSBT") (class "Default")
      (node (ref "D1") (pin "C") (pinfunction "C_C") (pintype "passive"))
      (node (ref "IC1") (pin "1") (pinfunction "CSBO_1") (pintype "bidirectional"))
    )
    (net (code "28") (name "FSM") (class "Default")
      (node (ref "CF1") (pin "1") (pinfunction "1_1") (pintype "passive"))
      (node (ref "IC4") (pin "11") (pinfunction "X3_11") (pintype "bidirectional"))
      (node (ref "RF1") (pin "1") (pinfunction "1_1") (pintype "passive"))
      (node (ref "RF2") (pin "2") (pinfunction "2_2") (pintype "passive"))
    )
    (net (code "29") (name "GND") (class "Default")
      (node (ref "C1") (pin "2") (pinfunction "2_2") (pintype "passive"))
      (node (ref "C12") (pin "2") (pinfunction "2_2") (pintype "passive"))
      (node (ref "C2") (pin "2") (pinfunction "2_2") (pintype "passive"))
      (node (ref "C25") (pin "2") (pinfunction "2_2") (pintype "passive"))
      (node (ref "C3") (pin "2") (pinfunction "2_2") (pintype "passive"))
      (node (ref "C4") (pin "2") (pinfunction "2_2") (pintype "passive"))
      (node (ref "C5") (pin "2") (pinfunction "2_2") (pintype "passive"))
      (node (ref "C6") (pin "2") (pinfunction "2_2") (pintype "passive"))
      (node (ref "C7") (pin "2") (pinfunction "2_2") (pintype "passive"))
      (node (ref "C9") (pin "2") (pinfunction "2_2") (pintype "passive"))
      (node (ref "CD1") (pin "A") (pinfunction "A_A") (pintype "passive"))
      (node (ref "CF1") (pin "2") (pinfunction "2_2") (pintype "passive"))
      (node (ref "CS1") (pin "2") (pinfunction "2_2") (pintype "passive"))
      (node (ref "D4") (pin "A") (pinfunction "A_A") (pintype "passive"))
      (node (ref "IC1") (pin "29") (pinfunction "C0_29") (pintype "bidirectional"))
      (node (ref "IC1") (pin "30") (pinfunction "V-_30") (pintype "bidirectional"))
      (node (ref "IC2") (pin "2") (pinfunction "V-_2") (pintype "power_in"))
      (node (ref "IC3") (pin "4") (pinfunction "V-_4") (pintype "power_in"))
      (node (ref "IC4") (pin "6") (pinfunction "INH_6") (pintype "input"))
      (node (ref "IC4") (pin "7") (pinfunction "VEE_7") (pintype "power_in"))
      (node (ref "IC4") (pin "8") (pinfunction "GND_8") (pintype "power_in"))
      (node (ref "LED1") (pin "C") (pinfunction "C_C") (pintype "passive"))
      (node (ref "MC1") (pin "2") (pinfunction "2_2") (pintype "passive"))
      (node (ref "RF2") (pin "1") (pinfunction "1_1") (pintype "passive"))
      (node (ref "RP1") (pin "P$1") (pinfunction "1_P$1") (pintype "passive"))
      (node (ref "SJ1") (pin "3") (pinfunction "3_3") (pintype "passive"))
      (node (ref "SJ2") (pin "1") (pinfunction "1_1") (pintype "passive"))
      (node (ref "X3") (pin "2") (pinfunction "2_2") (pintype "passive"))
      (node (ref "X4") (pin "P$10") (pinfunction "10_P$10") (pintype "passive"))
      (node (ref "X4") (pin "P$11") (pinfunction "11_P$11") (pintype "passive"))
      (node (ref "X4") (pin "P$12") (pinfunction "12_P$12") (pintype "passive"))
      (node (ref "X4") (pin "P$7") (pinfunction "7_P$7") (pintype "passive"))
      (node (ref "X4") (pin "P$8") (pinfunction "8_P$8") (pintype "passive"))
      (node (ref "X4") (pin "P$9") (pinfunction "9_P$9") (pintype "passive"))
      (node (ref "X5") (pin "P$14") (pinfunction "14_P$14") (pintype "passive"))
      (node (ref "X5") (pin "P$7") (pinfunction "7_P$7") (pintype "passive"))
    )
    (net (code "30") (name "GPIO1") (class "Default")
      (node (ref "IC1") (pin "38") (pinfunction "GPIO1_38") (pintype "bidirectional"))
      (node (ref "IC4") (pin "10") (pinfunction "A_10") (pintype "input"))
      (node (ref "R22") (pin "1") (pinfunction "1_1") (pintype "passive"))
    )
    (net (code "31") (name "GPIO2") (class "Default")
      (node (ref "IC1") (pin "39") (pinfunction "GPIO2_39") (pintype "bidirectional"))
      (node (ref "IC4") (pin "9") (pinfunction "B_9") (pintype "input"))
      (node (ref "R21") (pin "1") (pinfunction "1_1") (pintype "passive"))
    )
    (net (code "32") (name "MUX1") (class "Default")
      (node (ref "IC3") (pin "3") (pinfunction "+IN_3") (pintype "input"))
      (node (ref "IC4") (pin "13") (pinfunction "X_13") (pintype "bidirectional"))
    )
    (net (code "33") (name "MUX2") (class "Default")
      (node (ref "IC3") (pin "5") (pinfunction "+IN_5") (pintype "input"))
      (node (ref "IC4") (pin "3") (pinfunction "Y_3") (pintype "bidirectional"))
    )
    (net (code "34") (name "Net-(D1-PadA)") (class "Default")
      (node (ref "D1") (pin "A") (pinfunction "A_A") (pintype "passive"))
      (node (ref "R3") (pin "1") (pinfunction "1_1") (pintype "passive"))
    )
    (net (code "35") (name "Net-(D2-PadA)") (class "Default")
      (node (ref "D2") (pin "A") (pinfunction "A_A") (pintype "passive"))
      (node (ref "R4") (pin "1") (pinfunction "1_1") (pintype "passive"))
    )
    (net (code "36") (name "Net-(D3-PadA)") (class "Default")
      (node (ref "D3") (pin "A") (pinfunction "A_A") (pintype "passive"))
      (node (ref "R5") (pin "1") (pinfunction "1_1") (pintype "passive"))
    )
    (net (code "37") (name "Net-(IC1-WDTB)") (class "Default")
      (node (ref "IC1") (pin "37") (pinfunction "WDTB_37") (pintype "bidirectional"))
      (node (ref "R9") (pin "2") (pinfunction "2_2") (pintype "passive"))
    )
    (net (code "38") (name "Net-(LED1-PadA)") (class "Default")
      (node (ref "LED1") (pin "A") (pinfunction "A_A") (pintype "passive"))
      (node (ref "R10") (pin "1") (pinfunction "1_1") (pintype "passive"))
    )
    (net (code "39") (name "Net-(LED2-PadA)") (class "Default")
      (node (ref "LED2") (pin "A") (pinfunction "A_A") (pintype "passive"))
      (node (ref "R11") (pin "1") (pinfunction "1_1") (pintype "passive"))
    )
    (net (code "40") (name "Net-(LED3-PadA)") (class "Default")
      (node (ref "LED3") (pin "A") (pinfunction "A_A") (pintype "passive"))
      (node (ref "R12") (pin "1") (pinfunction "1_1") (pintype "passive"))
    )
    (net (code "41") (name "Net-(LED4-PadA)") (class "Default")
      (node (ref "LED4") (pin "A") (pinfunction "A_A") (pintype "passive"))
      (node (ref "R13") (pin "1") (pinfunction "1_1") (pintype "passive"))
    )
    (net (code "42") (name "Net-(LED5-PadA)") (class "Default")
      (node (ref "LED5") (pin "A") (pinfunction "A_A") (pintype "passive"))
      (node (ref "R14") (pin "1") (pinfunction "1_1") (pintype "passive"))
    )
    (net (code "43") (name "Net-(LED6-PadA)") (class "Default")
      (node (ref "LED6") (pin "A") (pinfunction "A_A") (pintype "passive"))
      (node (ref "R19") (pin "1") (pinfunction "1_1") (pintype "passive"))
    )
    (net (code "44") (name "Net-(LED7-PadA)") (class "Default")
      (node (ref "LED7") (pin "A") (pinfunction "A_A") (pintype "passive"))
      (node (ref "R20") (pin "1") (pinfunction "1_1") (pintype "passive"))
    )
    (net (code "45") (name "Net-(LED8-PadA)") (class "Default")
      (node (ref "LED8") (pin "A") (pinfunction "A_A") (pintype "passive"))
      (node (ref "R23") (pin "1") (pinfunction "1_1") (pintype "passive"))
    )
    (net (code "46") (name "Net-(LED9-PadA)") (class "Default")
      (node (ref "LED9") (pin "A") (pinfunction "A_A") (pintype "passive"))
      (node (ref "R24") (pin "1") (pinfunction "1_1") (pintype "passive"))
    )
    (net (code "47") (name "Net-(LED10-PadA)") (class "Default")
      (node (ref "LED10") (pin "A") (pinfunction "A_A") (pintype "passive"))
      (node (ref "R25") (pin "1") (pinfunction "1_1") (pintype "passive"))
    )
    (net (code "48") (name "Net-(LED11-PadA)") (class "Default")
      (node (ref "LED11") (pin "A") (pinfunction "A_A") (pintype "passive"))
      (node (ref "R26") (pin "1") (pinfunction "1_1") (pintype "passive"))
    )
    (net (code "49") (name "Net-(LED12-PadA)") (class "Default")
      (node (ref "LED12") (pin "A") (pinfunction "A_A") (pintype "passive"))
      (node (ref "R27") (pin "1") (pinfunction "1_1") (pintype "passive"))
    )
    (net (code "50") (name "Net-(QB1-D)") (class "Default")
      (node (ref "QB1") (pin "3") (pinfunction "D_3") (pintype "passive"))
      (node (ref "R10") (pin "2") (pinfunction "2_2") (pintype "passive"))
      (node (ref "RP1") (pin "P$2") (pinfunction "2_P$2") (pintype "passive"))
    )
    (net (code "51") (name "Net-(QB1-G)") (class "Default")
      (node (ref "GR1") (pin "2") (pinfunction "2_2") (pintype "passive"))
      (node (ref "QB1") (pin "1") (pinfunction "G_1") (pintype "passive"))
    )
    (net (code "52") (name "Net-(QB2-D)") (class "Default")
      (node (ref "QB2") (pin "3") (pinfunction "D_3") (pintype "passive"))
      (node (ref "R11") (pin "2") (pinfunction "2_2") (pintype "passive"))
      (node (ref "RP2") (pin "P$2") (pinfunction "2_P$2") (pintype "passive"))
    )
    (net (code "53") (name "Net-(QB2-G)") (class "Default")
      (node (ref "GR2") (pin "2") (pinfunction "2_2") (pintype "passive"))
      (node (ref "QB2") (pin "1") (pinfunction "G_1") (pintype "passive"))
    )
    (net (code "54") (name "Net-(QB3-D)") (class "Default")
      (node (ref "QB3") (pin "3") (pinfunction "D_3") (pintype "passive"))
      (node (ref "R12") (pin "2") (pinfunction "2_2") (pintype "passive"))
      (node (ref "RP3") (pin "P$2") (pinfunction "2_P$2") (pintype "passive"))
    )
    (net (code "55") (name "Net-(QB3-G)") (class "Default")
      (node (ref "GR3") (pin "2") (pinfunction "2_2") (pintype "passive"))
      (node (ref "QB3") (pin "1") (pinfunction "G_1") (pintype "passive"))
    )
    (net (code "56") (name "Net-(QB4-D)") (class "Default")
      (node (ref "QB4") (pin "3") (pinfunction "D_3") (pintype "passive"))
      (node (ref "R13") (pin "2") (pinfunction "2_2") (pintype "passive"))
      (node (ref "RP4") (pin "P$2") (pinfunction "2_P$2") (pintype "passive"))
    )
    (net (code "57") (name "Net-(QB4-G)") (class "Default")
      (node (ref "GR4") (pin "2") (pinfunction "2_2") (pintype "passive"))
      (node (ref "QB4") (pin "1") (pinfunction "G_1") (pintype "passive"))
    )
    (net (code "58") (name "Net-(QB5-D)") (class "Default")
      (node (ref "QB5") (pin "3") (pinfunction "D_3") (pintype "passive"))
      (node (ref "R14") (pin "2") (pinfunction "2_2") (pintype "passive"))
      (node (ref "RP5") (pin "P$2") (pinfunction "2_P$2") (pintype "passive"))
    )
    (net (code "59") (name "Net-(QB5-G)") (class "Default")
      (node (ref "GR5") (pin "2") (pinfunction "2_2") (pintype "passive"))
      (node (ref "QB5") (pin "1") (pinfunction "G_1") (pintype "passive"))
    )
    (net (code "60") (name "Net-(QB6-D)") (class "Default")
      (node (ref "QB6") (pin "3") (pinfunction "D_3") (pintype "passive"))
      (node (ref "R19") (pin "2") (pinfunction "2_2") (pintype "passive"))
      (node (ref "RP6") (pin "P$2") (pinfunction "2_P$2") (pintype "passive"))
    )
    (net (code "61") (name "Net-(QB6-G)") (class "Default")
      (node (ref "GR6") (pin "2") (pinfunction "2_2") (pintype "passive"))
      (node (ref "QB6") (pin "1") (pinfunction "G_1") (pintype "passive"))
    )
    (net (code "62") (name "Net-(QB7-D)") (class "Default")
      (node (ref "QB7") (pin "3") (pinfunction "D_3") (pintype "passive"))
      (node (ref "R20") (pin "2") (pinfunction "2_2") (pintype "passive"))
      (node (ref "RP7") (pin "P$2") (pinfunction "2_P$2") (pintype "passive"))
    )
    (net (code "63") (name "Net-(QB7-G)") (class "Default")
      (node (ref "GR7") (pin "2") (pinfunction "2_2") (pintype "passive"))
      (node (ref "QB7") (pin "1") (pinfunction "G_1") (pintype "passive"))
    )
    (net (code "64") (name "Net-(QB8-D)") (class "Default")
      (node (ref "QB8") (pin "3") (pinfunction "D_3") (pintype "passive"))
      (node (ref "R23") (pin "2") (pinfunction "2_2") (pintype "passive"))
      (node (ref "RP8") (pin "P$2") (pinfunction "2_P$2") (pintype "passive"))
    )
    (net (code "65") (name "Net-(QB8-G)") (class "Default")
      (node (ref "GR8") (pin "2") (pinfunction "2_2") (pintype "passive"))
      (node (ref "QB8") (pin "1") (pinfunction "G_1") (pintype "passive"))
    )
    (net (code "66") (name "Net-(QB9-D)") (class "Default")
      (node (ref "QB9") (pin "3") (pinfunction "D_3") (pintype "passive"))
      (node (ref "R24") (pin "2") (pinfunction "2_2") (pintype "passive"))
      (node (ref "RP9") (pin "P$2") (pinfunction "2_P$2") (pintype "passive"))
    )
    (net (code "67") (name "Net-(QB9-G)") (class "Default")
      (node (ref "GR9") (pin "2") (pinfunction "2_2") (pintype "passive"))
      (node (ref "QB9") (pin "1") (pinfunction "G_1") (pintype "passive"))
    )
    (net (code "68") (name "Net-(QB10-D)") (class "Default")
      (node (ref "QB10") (pin "3") (pinfunction "D_3") (pintype "passive"))
      (node (ref "R25") (pin "2") (pinfunction "2_2") (pintype "passive"))
      (node (ref "RP10") (pin "P$2") (pinfunction "2_P$2") (pintype "passive"))
    )
    (net (code "69") (name "Net-(QB10-G)") (class "Default")
      (node (ref "GR10") (pin "2") (pinfunction "2_2") (pintype "passive"))
      (node (ref "QB10") (pin "1") (pinfunction "G_1") (pintype "passive"))
    )
    (net (code "70") (name "Net-(QB11-D)") (class "Default")
      (node (ref "QB11") (pin "3") (pinfunction "D_3") (pintype "passive"))
      (node (ref "R26") (pin "2") (pinfunction "2_2") (pintype "passive"))
      (node (ref "RP11") (pin "P$2") (pinfunction "2_P$2") (pintype "passive"))
    )
    (net (code "71") (name "Net-(QB11-G)") (class "Default")
      (node (ref "GR11") (pin "2") (pinfunction "2_2") (pintype "passive"))
      (node (ref "QB11") (pin "1") (pinfunction "G_1") (pintype "passive"))
    )
    (net (code "72") (name "Net-(QB12-D)") (class "Default")
      (node (ref "QB12") (pin "3") (pinfunction "D_3") (pintype "passive"))
      (node (ref "R27") (pin "2") (pinfunction "2_2") (pintype "passive"))
      (node (ref "RP12") (pin "P$2") (pinfunction "2_P$2") (pintype "passive"))
    )
    (net (code "73") (name "Net-(QB12-G)") (class "Default")
      (node (ref "GR12") (pin "2") (pinfunction "2_2") (pintype "passive"))
      (node (ref "QB12") (pin "1") (pinfunction "G_1") (pintype "passive"))
    )
    (net (code "74") (name "Net-(R3-Pad2)") (class "Default")
      (node (ref "R3") (pin "2") (pinfunction "2_2") (pintype "passive"))
      (node (ref "X1") (pin "1") (pinfunction "1_1") (pintype "passive"))
    )
    (net (code "75") (name "Net-(R4-Pad2)") (class "Default")
      (node (ref "R4") (pin "2") (pinfunction "2_2") (pintype "passive"))
      (node (ref "X1") (pin "2") (pinfunction "2_2") (pintype "passive"))
    )
    (net (code "76") (name "Net-(R5-Pad2)") (class "Default")
      (node (ref "R5") (pin "2") (pinfunction "2_2") (pintype "passive"))
      (node (ref "X1") (pin "3") (pinfunction "3_3") (pintype "passive"))
    )
    (net (code "77") (name "Net-(R6-Pad2)") (class "Default")
      (node (ref "R6") (pin "2") (pinfunction "2_2") (pintype "passive"))
      (node (ref "X2") (pin "1") (pinfunction "1_1") (pintype "passive"))
    )
    (net (code "78") (name "Net-(R7-Pad2)") (class "Default")
      (node (ref "R7") (pin "2") (pinfunction "2_2") (pintype "passive"))
      (node (ref "X2") (pin "2") (pinfunction "2_2") (pintype "passive"))
    )
    (net (code "79") (name "Net-(R8-Pad2)") (class "Default")
      (node (ref "R8") (pin "2") (pinfunction "2_2") (pintype "passive"))
      (node (ref "X2") (pin "3") (pinfunction "3_3") (pintype "passive"))
    )
    (net (code "80") (name "S1") (class "Default")
      (node (ref "GR1") (pin "1") (pinfunction "1_1") (pintype "passive"))
      (node (ref "IC1") (pin "28") (pinfunction "S1_28") (pintype "bidirectional"))
    )
    (net (code "81") (name "S2") (class "Default")
      (node (ref "GR2") (pin "1") (pinfunction "1_1") (pintype "passive"))
      (node (ref "IC1") (pin "26") (pinfunction "S2_26") (pintype "bidirectional"))
    )
    (net (code "82") (name "S3") (class "Default")
      (node (ref "GR3") (pin "1") (pinfunction "1_1") (pintype "passive"))
      (node (ref "IC1") (pin "24") (pinfunction "S3_24") (pintype "bidirectional"))
    )
    (net (code "83") (name "S4") (class "Default")
      (node (ref "GR4") (pin "1") (pinfunction "1_1") (pintype "passive"))
      (node (ref "IC1") (pin "22") (pinfunction "S4_22") (pintype "bidirectional"))
    )
    (net (code "84") (name "S5") (class "Default")
      (node (ref "GR5") (pin "1") (pinfunction "1_1") (pintype "passive"))
      (node (ref "IC1") (pin "20") (pinfunction "S5_20") (pintype "bidirectional"))
    )
    (net (code "85") (name "S6") (class "Default")
      (node (ref "GR6") (pin "1") (pinfunction "1_1") (pintype "passive"))
      (node (ref "IC1") (pin "18") (pinfunction "S6_18") (pintype "bidirectional"))
    )
    (net (code "86") (name "S7") (class "Default")
      (node (ref "GR7") (pin "1") (pinfunction "1_1") (pintype "passive"))
      (node (ref "IC1") (pin "16") (pinfunction "S7_16") (pintype "bidirectional"))
    )
    (net (code "87") (name "S8") (class "Default")
      (node (ref "GR8") (pin "1") (pinfunction "1_1") (pintype "passive"))
      (node (ref "IC1") (pin "14") (pinfunction "S8_14") (pintype "bidirectional"))
    )
    (net (code "88") (name "S9") (class "Default")
      (node (ref "GR9") (pin "1") (pinfunction "1_1") (pintype "passive"))
      (node (ref "IC1") (pin "12") (pinfunction "S9_12") (pintype "bidirectional"))
    )
    (net (code "89") (name "S10") (class "Default")
      (node (ref "GR10") (pin "1") (pinfunction "1_1") (pintype "passive"))
      (node (ref "IC1") (pin "10") (pinfunction "S10_10") (pintype "bidirectional"))
    )
    (net (code "90") (name "S11") (class "Default")
      (node (ref "GR11") (pin "1") (pinfunction "1_1") (pintype "passive"))
      (node (ref "IC1") (pin "8") (pinfunction "S11_8") (pintype "bidirectional"))
    )
    (net (code "91") (name "S12") (class "Default")
      (node (ref "GR12") (pin "1") (pinfunction "1_1") (pintype "passive"))
      (node (ref "IC1") (pin "6") (pinfunction "S12_6") (pintype "bidirectional"))
    )
    (net (code "92") (name "SCKB") (class "Default")
      (node (ref "IC1") (pin "41") (pinfunction "SCKI_41") (pintype "bidirectional"))
      (node (ref "R8") (pin "1") (pinfunction "1_1") (pintype "passive"))
    )
    (net (code "93") (name "SCKT") (class "Default")
      (node (ref "D3") (pin "C") (pinfunction "C_C") (pintype "passive"))
      (node (ref "IC1") (pin "3") (pinfunction "SCKO_3") (pintype "bidirectional"))
    )
    (net (code "94") (name "SDIB") (class "Default")
      (node (ref "IC1") (pin "42") (pinfunction "SDI_42") (pintype "bidirectional"))
      (node (ref "R7") (pin "1") (pinfunction "1_1") (pintype "passive"))
    )
    (net (code "95") (name "SDOB") (class "Default")
      (node (ref "IC1") (pin "43") (pinfunction "SDO_43") (pintype "bidirectional"))
      (node (ref "X3") (pin "1") (pinfunction "1_1") (pintype "passive"))
    )
    (net (code "96") (name "SDOT") (class "Default")
      (node (ref "D2") (pin "C") (pinfunction "C_C") (pintype "passive"))
      (node (ref "IC1") (pin "2") (pinfunction "SDOI_2") (pintype "bidirectional"))
    )
    (net (code "97") (name "TOS") (class "Default")
      (node (ref "IC1") (pin "36") (pinfunction "TOS_36") (pintype "bidirectional"))
      (node (ref "SJ2") (pin "2") (pinfunction "2_2") (pintype "passive"))
    )
    (net (code "98") (name "TSM1") (class "Default")
      (node (ref "C25") (pin "1") (pinfunction "1_1") (pintype "passive"))
      (node (ref "IC4") (pin "5") (pinfunction "Y1_5") (pintype "bidirectional"))
      (node (ref "R15") (pin "2") (pinfunction "2_2") (pintype "passive"))
      (node (ref "X4") (pin "P$1") (pinfunction "1_P$1") (pintype "passive"))
    )
    (net (code "99") (name "TSM2") (class "Default")
      (node (ref "C1") (pin "1") (pinfunction "1_1") (pintype "passive"))
      (node (ref "IC4") (pin "2") (pinfunction "Y2_2") (pintype "bidirectional"))
      (node (ref "R16") (pin "2") (pinfunction "2_2") (pintype "passive"))
      (node (ref "X4") (pin "P$2") (pinfunction "2_P$2") (pintype "passive"))
    )
    (net (code "100") (name "TSM3") (class "Default")
      (node (ref "C2") (pin "1") (pinfunction "1_1") (pintype "passive"))
      (node (ref "IC4") (pin "1") (pinfunction "Y0_1") (pintype "bidirectional"))
      (node (ref "R17") (pin "2") (pinfunction "2_2") (pintype "passive"))
      (node (ref "X4") (pin "P$3") (pinfunction "3_P$3") (pintype "passive"))
    )
    (net (code "101") (name "TSM4") (class "Default")
      (node (ref "C3") (pin "1") (pinfunction "1_1") (pintype "passive"))
      (node (ref "IC4") (pin "15") (pinfunction "X2_15") (pintype "bidirectional"))
      (node (ref "R18") (pin "2") (pinfunction "2_2") (pintype "passive"))
      (node (ref "X4") (pin "P$4") (pinfunction "4_P$4") (pintype "passive"))
    )
    (net (code "102") (name "TSM5") (class "Default")
      (node (ref "C6") (pin "1") (pinfunction "1_1") (pintype "passive"))
      (node (ref "IC4") (pin "12") (pinfunction "X0_12") (pintype "bidirectional"))
      (node (ref "R1") (pin "2") (pinfunction "2_2") (pintype "passive"))
      (node (ref "X4") (pin "P$6") (pinfunction "6_P$6") (pintype "passive"))
    )
    (net (code "103") (name "TSM6") (class "Default")
      (node (ref "C5") (pin "1") (pinfunction "1_1") (pintype "passive"))
      (node (ref "IC4") (pin "14") (pinfunction "X1_14") (pintype "bidirectional"))
      (node (ref "R2") (pin "2") (pinfunction "2_2") (pintype "passive"))
      (node (ref "X4") (pin "P$5") (pinfunction "5_P$5") (pintype "passive"))
    )
    (net (code "104") (name "VMODE") (class "Default")
      (node (ref "IC1") (pin "40") (pinfunction "VMODE_40") (pintype "bidirectional"))
      (node (ref "SJ1") (pin "2") (pinfunction "2_2") (pintype "passive"))
    )
    (net (code "105") (name "VREF") (class "Default")
      (node (ref "C7") (pin "1") (pinfunction "1_1") (pintype "passive"))
      (node (ref "IC1") (pin "34") (pinfunction "VREF_34") (pintype "bidirectional"))
      (node (ref "IC2") (pin "3") (pinfunction "+IN_3") (pintype "input"))
    )
    (net (code "106") (name "VREFP") (class "Default")
      (node (ref "IC2") (pin "1") (pinfunction "OUT_1") (pintype "output"))
      (node (ref "IC2") (pin "4") (pinfunction "-IN_4") (pintype "input"))
      (node (ref "R1") (pin "1") (pinfunction "1_1") (pintype "passive"))
      (node (ref "R15") (pin "1") (pinfunction "1_1") (pintype "passive"))
      (node (ref "R16") (pin "1") (pinfunction "1_1") (pintype "passive"))
      (node (ref "R17") (pin "1") (pinfunction "1_1") (pintype "passive"))
      (node (ref "R18") (pin "1") (pinfunction "1_1") (pintype "passive"))
      (node (ref "R2") (pin "1") (pinfunction "1_1") (pintype "passive"))
    )
    (net (code "107") (name "VTEMP1") (class "Default")
      (node (ref "IC1") (pin "32") (pinfunction "VTEMP1_32") (pintype "bidirectional"))
      (node (ref "IC3") (pin "1") (pinfunction "OUT_1") (pintype "output"))
      (node (ref "IC3") (pin "2") (pinfunction "-IN_2") (pintype "input"))
    )
    (net (code "108") (name "VTEMP2") (class "Default")
      (node (ref "IC1") (pin "33") (pinfunction "VTEMP2_33") (pintype "bidirectional"))
      (node (ref "IC3") (pin "6") (pinfunction "-IN_6") (pintype "input"))
      (node (ref "IC3") (pin "7") (pinfunction "OUT_7") (pintype "output"))
    )
    (net (code "109") (name "unconnected-(IC4A-Y3-Pad4)") (class "Default")
      (node (ref "IC4") (pin "4") (pinfunction "Y3_4") (pintype "bidirectional"))
    )
  )
)
